# STM32H745.net
KiCad netlist of a schematic drawn in Altium Designer
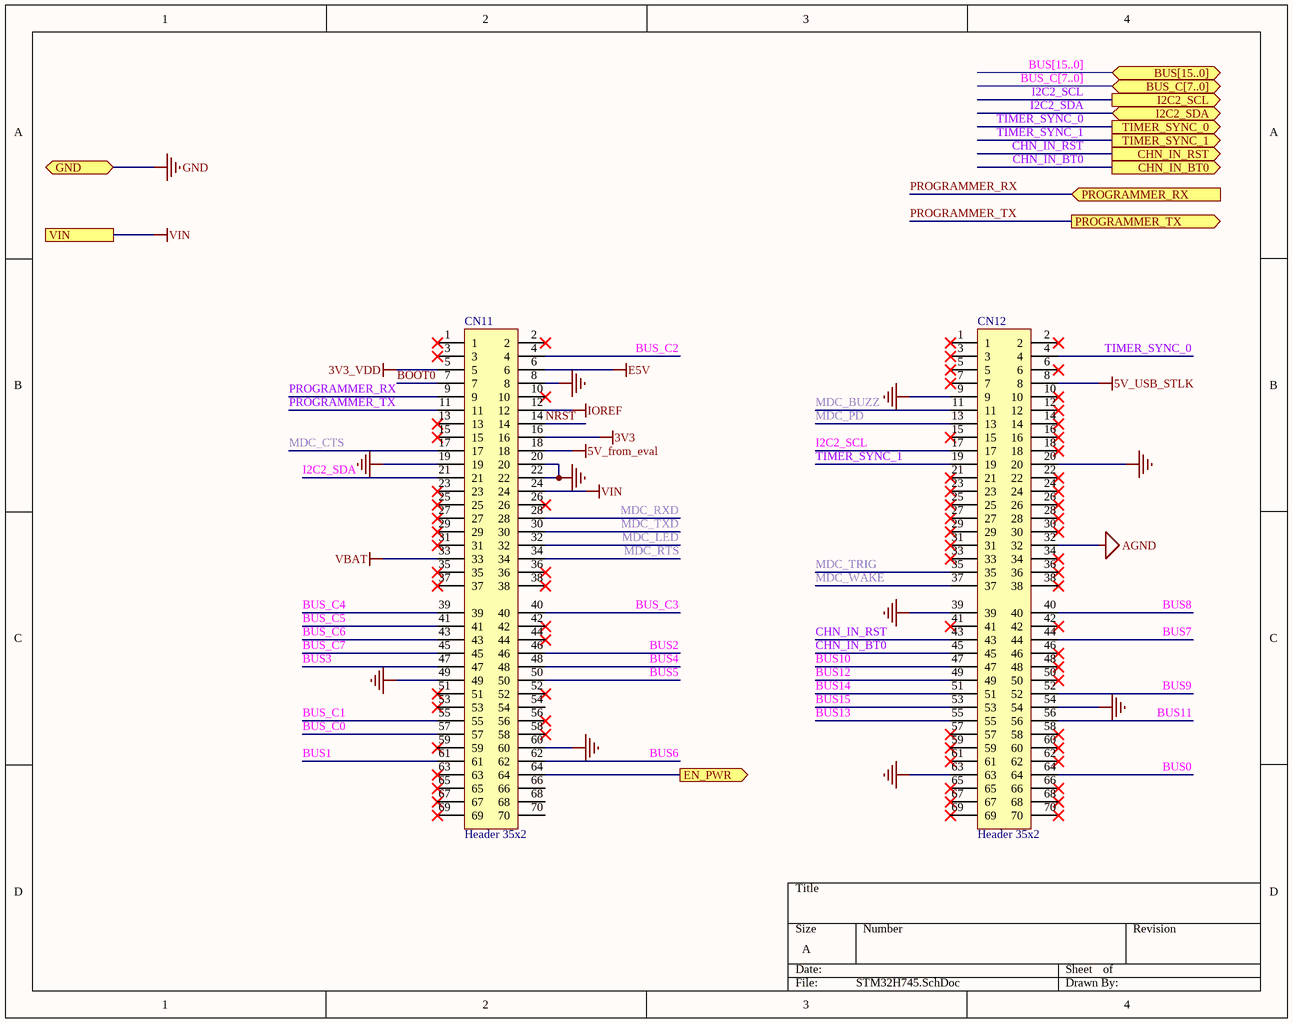
[diagram p0: STM32H745.SchDoc]

(export (version "E")
  (design (tool "Eeschema 10.0.6"))
  (components
    (comp (ref "CN11")
      (value "Header 35x2")
      (footprint "HDR_2x36_2R54_V_M")
      (description "Header, 35x2, 2,54mm, VR, TH, Height 5.84mm/2.54mm")
      (libsource (lib "mantarray_library") (part "MCD-01210"))
    )
    (comp (ref "CN12")
      (value "Header 35x2")
      (footprint "HDR_2x36_2R54_V_M")
      (description "Header, 35x2, 2,54mm, VR, TH, Height 5.84mm/2.54mm")
      (libsource (lib "mantarray_library") (part "MCD-01210"))
    )
  )
  (nets
    (net (code "1") (name "/BOOT0") (class "Default")
      (node (ref "CN11") (pin "7") (pinfunction "7_7") (pintype "passive"))
    )
    (net (code "2") (name "/BUS0") (class "Default")
      (node (ref "CN12") (pin "64") (pinfunction "64_64") (pintype "passive"))
    )
    (net (code "3") (name "/BUS1") (class "Default")
      (node (ref "CN11") (pin "61") (pinfunction "61_61") (pintype "passive"))
    )
    (net (code "4") (name "/BUS2") (class "Default")
      (node (ref "CN11") (pin "46") (pinfunction "46_46") (pintype "passive"))
    )
    (net (code "5") (name "/BUS3") (class "Default")
      (node (ref "CN11") (pin "47") (pinfunction "47_47") (pintype "passive"))
    )
    (net (code "6") (name "/BUS4") (class "Default")
      (node (ref "CN11") (pin "48") (pinfunction "48_48") (pintype "passive"))
    )
    (net (code "7") (name "/BUS5") (class "Default")
      (node (ref "CN11") (pin "50") (pinfunction "50_50") (pintype "passive"))
    )
    (net (code "8") (name "/BUS6") (class "Default")
      (node (ref "CN11") (pin "62") (pinfunction "62_62") (pintype "passive"))
    )
    (net (code "9") (name "/BUS7") (class "Default")
      (node (ref "CN12") (pin "44") (pinfunction "44_44") (pintype "passive"))
    )
    (net (code "10") (name "/BUS8") (class "Default")
      (node (ref "CN12") (pin "40") (pinfunction "40_40") (pintype "passive"))
    )
    (net (code "11") (name "/BUS9") (class "Default")
      (node (ref "CN12") (pin "52") (pinfunction "52_52") (pintype "passive"))
    )
    (net (code "12") (name "/BUS10") (class "Default")
      (node (ref "CN12") (pin "47") (pinfunction "47_47") (pintype "passive"))
    )
    (net (code "13") (name "/BUS11") (class "Default")
      (node (ref "CN12") (pin "56") (pinfunction "56_56") (pintype "passive"))
    )
    (net (code "14") (name "/BUS12") (class "Default")
      (node (ref "CN12") (pin "49") (pinfunction "49_49") (pintype "passive"))
    )
    (net (code "15") (name "/BUS13") (class "Default")
      (node (ref "CN12") (pin "55") (pinfunction "55_55") (pintype "passive"))
    )
    (net (code "16") (name "/BUS14") (class "Default")
      (node (ref "CN12") (pin "51") (pinfunction "51_51") (pintype "passive"))
    )
    (net (code "17") (name "/BUS15") (class "Default")
      (node (ref "CN12") (pin "53") (pinfunction "53_53") (pintype "passive"))
    )
    (net (code "19") (name "/BUS_C0") (class "Default")
      (node (ref "CN11") (pin "57") (pinfunction "57_57") (pintype "passive"))
    )
    (net (code "20") (name "/BUS_C1") (class "Default")
      (node (ref "CN11") (pin "55") (pinfunction "55_55") (pintype "passive"))
    )
    (net (code "21") (name "/BUS_C2") (class "Default")
      (node (ref "CN11") (pin "4") (pinfunction "4_4") (pintype "passive"))
    )
    (net (code "22") (name "/BUS_C3") (class "Default")
      (node (ref "CN11") (pin "40") (pinfunction "40_40") (pintype "passive"))
    )
    (net (code "23") (name "/BUS_C4") (class "Default")
      (node (ref "CN11") (pin "39") (pinfunction "39_39") (pintype "passive"))
    )
    (net (code "24") (name "/BUS_C5") (class "Default")
      (node (ref "CN11") (pin "41") (pinfunction "41_41") (pintype "passive"))
    )
    (net (code "25") (name "/BUS_C6") (class "Default")
      (node (ref "CN11") (pin "43") (pinfunction "43_43") (pintype "passive"))
    )
    (net (code "26") (name "/BUS_C7") (class "Default")
      (node (ref "CN11") (pin "45") (pinfunction "45_45") (pintype "passive"))
    )
    (net (code "28") (name "/CHN_IN_BT0") (class "Default")
      (node (ref "CN12") (pin "45") (pinfunction "45_45") (pintype "passive"))
    )
    (net (code "29") (name "/CHN_IN_RST") (class "Default")
      (node (ref "CN12") (pin "43") (pinfunction "43_43") (pintype "passive"))
    )
    (net (code "30") (name "/EN_PWR") (class "Default")
      (node (ref "CN11") (pin "64") (pinfunction "64_64") (pintype "passive"))
    )
    (net (code "31") (name "/I2C2_SCL") (class "Default")
      (node (ref "CN12") (pin "17") (pinfunction "17_17") (pintype "passive"))
    )
    (net (code "32") (name "/I2C2_SDA") (class "Default")
      (node (ref "CN11") (pin "21") (pinfunction "21_21") (pintype "passive"))
    )
    (net (code "33") (name "/MDC_BUZZ") (class "Default")
      (node (ref "CN12") (pin "11") (pinfunction "11_11") (pintype "passive"))
    )
    (net (code "34") (name "/MDC_CTS") (class "Default")
      (node (ref "CN11") (pin "17") (pinfunction "17_17") (pintype "passive"))
    )
    (net (code "35") (name "/MDC_LED") (class "Default")
      (node (ref "CN11") (pin "32") (pinfunction "32_32") (pintype "passive"))
    )
    (net (code "36") (name "/MDC_PD") (class "Default")
      (node (ref "CN12") (pin "13") (pinfunction "13_13") (pintype "passive"))
    )
    (net (code "37") (name "/MDC_RTS") (class "Default")
      (node (ref "CN11") (pin "34") (pinfunction "34_34") (pintype "passive"))
    )
    (net (code "38") (name "/MDC_RXD") (class "Default")
      (node (ref "CN11") (pin "28") (pinfunction "28_28") (pintype "passive"))
    )
    (net (code "39") (name "/MDC_TRIG") (class "Default")
      (node (ref "CN12") (pin "35") (pinfunction "35_35") (pintype "passive"))
    )
    (net (code "40") (name "/MDC_TXD") (class "Default")
      (node (ref "CN11") (pin "30") (pinfunction "30_30") (pintype "passive"))
    )
    (net (code "41") (name "/MDC_WAKE") (class "Default")
      (node (ref "CN12") (pin "37") (pinfunction "37_37") (pintype "passive"))
    )
    (net (code "42") (name "/NRST") (class "Default")
      (node (ref "CN11") (pin "14") (pinfunction "14_14") (pintype "passive"))
    )
    (net (code "43") (name "/PROGRAMMER_RX") (class "Default")
      (node (ref "CN11") (pin "9") (pinfunction "9_9") (pintype "passive"))
    )
    (net (code "44") (name "/PROGRAMMER_TX") (class "Default")
      (node (ref "CN11") (pin "11") (pinfunction "11_11") (pintype "passive"))
    )
    (net (code "45") (name "/TIMER_SYNC_0") (class "Default")
      (node (ref "CN12") (pin "4") (pinfunction "4_4") (pintype "passive"))
    )
    (net (code "46") (name "/TIMER_SYNC_1") (class "Default")
      (node (ref "CN12") (pin "19") (pinfunction "19_19") (pintype "passive"))
    )
    (net (code "47") (name "3V3") (class "Default")
      (node (ref "CN11") (pin "16") (pinfunction "16_16") (pintype "passive"))
    )
    (net (code "48") (name "3V3_VDD") (class "Default")
      (node (ref "CN11") (pin "5") (pinfunction "5_5") (pintype "passive"))
    )
    (net (code "49") (name "5V_USB_STLK") (class "Default")
      (node (ref "CN12") (pin "8") (pinfunction "8_8") (pintype "passive"))
    )
    (net (code "50") (name "5V_from_eval") (class "Default")
      (node (ref "CN11") (pin "18") (pinfunction "18_18") (pintype "passive"))
    )
    (net (code "51") (name "AGND") (class "Default")
      (node (ref "CN12") (pin "32") (pinfunction "32_32") (pintype "passive"))
    )
    (net (code "52") (name "E5V") (class "Default")
      (node (ref "CN11") (pin "6") (pinfunction "6_6") (pintype "passive"))
    )
    (net (code "53") (name "GND") (class "Default")
      (node (ref "CN11") (pin "19") (pinfunction "19_19") (pintype "passive"))
      (node (ref "CN11") (pin "20") (pinfunction "20_20") (pintype "passive"))
      (node (ref "CN11") (pin "22") (pinfunction "22_22") (pintype "passive"))
      (node (ref "CN11") (pin "49") (pinfunction "49_49") (pintype "passive"))
      (node (ref "CN11") (pin "60") (pinfunction "60_60") (pintype "passive"))
      (node (ref "CN11") (pin "8") (pinfunction "8_8") (pintype "passive"))
      (node (ref "CN12") (pin "20") (pinfunction "20_20") (pintype "passive"))
      (node (ref "CN12") (pin "39") (pinfunction "39_39") (pintype "passive"))
      (node (ref "CN12") (pin "54") (pinfunction "54_54") (pintype "passive"))
      (node (ref "CN12") (pin "63") (pinfunction "63_63") (pintype "passive"))
      (node (ref "CN12") (pin "9") (pinfunction "9_9") (pintype "passive"))
    )
    (net (code "54") (name "IOREF") (class "Default")
      (node (ref "CN11") (pin "12") (pinfunction "12_12") (pintype "passive"))
    )
    (net (code "55") (name "VBAT") (class "Default")
      (node (ref "CN11") (pin "33") (pinfunction "33_33") (pintype "passive"))
    )
    (net (code "56") (name "VIN") (class "Default")
      (node (ref "CN11") (pin "24") (pinfunction "24_24") (pintype "passive"))
    )
    (net (code "57") (name "unconnected-(CN11-Pad1)") (class "Default")
      (node (ref "CN11") (pin "1") (pinfunction "1_1") (pintype "passive+no_connect"))
    )
    (net (code "58") (name "unconnected-(CN11-Pad2)") (class "Default")
      (node (ref "CN11") (pin "2") (pinfunction "2_2") (pintype "passive+no_connect"))
    )
    (net (code "59") (name "unconnected-(CN11-Pad3)") (class "Default")
      (node (ref "CN11") (pin "3") (pinfunction "3_3") (pintype "passive+no_connect"))
    )
    (net (code "60") (name "unconnected-(CN11-Pad10)") (class "Default")
      (node (ref "CN11") (pin "10") (pinfunction "10_10") (pintype "passive+no_connect"))
    )
    (net (code "61") (name "unconnected-(CN11-Pad13)") (class "Default")
      (node (ref "CN11") (pin "13") (pinfunction "13_13") (pintype "passive+no_connect"))
    )
    (net (code "62") (name "unconnected-(CN11-Pad15)") (class "Default")
      (node (ref "CN11") (pin "15") (pinfunction "15_15") (pintype "passive+no_connect"))
    )
    (net (code "63") (name "unconnected-(CN11-Pad23)") (class "Default")
      (node (ref "CN11") (pin "23") (pinfunction "23_23") (pintype "passive+no_connect"))
    )
    (net (code "64") (name "unconnected-(CN11-Pad25)") (class "Default")
      (node (ref "CN11") (pin "25") (pinfunction "25_25") (pintype "passive+no_connect"))
    )
    (net (code "65") (name "unconnected-(CN11-Pad26)") (class "Default")
      (node (ref "CN11") (pin "26") (pinfunction "26_26") (pintype "passive+no_connect"))
    )
    (net (code "66") (name "unconnected-(CN11-Pad27)") (class "Default")
      (node (ref "CN11") (pin "27") (pinfunction "27_27") (pintype "passive+no_connect"))
    )
    (net (code "67") (name "unconnected-(CN11-Pad29)") (class "Default")
      (node (ref "CN11") (pin "29") (pinfunction "29_29") (pintype "passive+no_connect"))
    )
    (net (code "68") (name "unconnected-(CN11-Pad31)") (class "Default")
      (node (ref "CN11") (pin "31") (pinfunction "31_31") (pintype "passive+no_connect"))
    )
    (net (code "69") (name "unconnected-(CN11-Pad35)") (class "Default")
      (node (ref "CN11") (pin "35") (pinfunction "35_35") (pintype "passive+no_connect"))
    )
    (net (code "70") (name "unconnected-(CN11-Pad36)") (class "Default")
      (node (ref "CN11") (pin "36") (pinfunction "36_36") (pintype "passive+no_connect"))
    )
    (net (code "71") (name "unconnected-(CN11-Pad37)") (class "Default")
      (node (ref "CN11") (pin "37") (pinfunction "37_37") (pintype "passive+no_connect"))
    )
    (net (code "72") (name "unconnected-(CN11-Pad38)") (class "Default")
      (node (ref "CN11") (pin "38") (pinfunction "38_38") (pintype "passive+no_connect"))
    )
    (net (code "73") (name "unconnected-(CN11-Pad42)") (class "Default")
      (node (ref "CN11") (pin "42") (pinfunction "42_42") (pintype "passive+no_connect"))
    )
    (net (code "74") (name "unconnected-(CN11-Pad44)") (class "Default")
      (node (ref "CN11") (pin "44") (pinfunction "44_44") (pintype "passive+no_connect"))
    )
    (net (code "75") (name "unconnected-(CN11-Pad51)") (class "Default")
      (node (ref "CN11") (pin "51") (pinfunction "51_51") (pintype "passive+no_connect"))
    )
    (net (code "76") (name "unconnected-(CN11-Pad52)") (class "Default")
      (node (ref "CN11") (pin "52") (pinfunction "52_52") (pintype "passive+no_connect"))
    )
    (net (code "77") (name "unconnected-(CN11-Pad53)") (class "Default")
      (node (ref "CN11") (pin "53") (pinfunction "53_53") (pintype "passive+no_connect"))
    )
    (net (code "78") (name "unconnected-(CN11-Pad54)") (class "Default")
      (node (ref "CN11") (pin "54") (pinfunction "54_54") (pintype "passive"))
    )
    (net (code "79") (name "unconnected-(CN11-Pad56)") (class "Default")
      (node (ref "CN11") (pin "56") (pinfunction "56_56") (pintype "passive+no_connect"))
    )
    (net (code "80") (name "unconnected-(CN11-Pad58)") (class "Default")
      (node (ref "CN11") (pin "58") (pinfunction "58_58") (pintype "passive+no_connect"))
    )
    (net (code "81") (name "unconnected-(CN11-Pad59)") (class "Default")
      (node (ref "CN11") (pin "59") (pinfunction "59_59") (pintype "passive+no_connect"))
    )
    (net (code "82") (name "unconnected-(CN11-Pad63)") (class "Default")
      (node (ref "CN11") (pin "63") (pinfunction "63_63") (pintype "passive+no_connect"))
    )
    (net (code "83") (name "unconnected-(CN11-Pad65)") (class "Default")
      (node (ref "CN11") (pin "65") (pinfunction "65_65") (pintype "passive+no_connect"))
    )
    (net (code "84") (name "unconnected-(CN11-Pad66)") (class "Default")
      (node (ref "CN11") (pin "66") (pinfunction "66_66") (pintype "passive"))
    )
    (net (code "85") (name "unconnected-(CN11-Pad67)") (class "Default")
      (node (ref "CN11") (pin "67") (pinfunction "67_67") (pintype "passive+no_connect"))
    )
    (net (code "86") (name "unconnected-(CN11-Pad68)") (class "Default")
      (node (ref "CN11") (pin "68") (pinfunction "68_68") (pintype "passive"))
    )
    (net (code "87") (name "unconnected-(CN11-Pad69)") (class "Default")
      (node (ref "CN11") (pin "69") (pinfunction "69_69") (pintype "passive+no_connect"))
    )
    (net (code "88") (name "unconnected-(CN11-Pad70)") (class "Default")
      (node (ref "CN11") (pin "70") (pinfunction "70_70") (pintype "passive"))
    )
    (net (code "89") (name "unconnected-(CN12-Pad1)") (class "Default")
      (node (ref "CN12") (pin "1") (pinfunction "1_1") (pintype "passive+no_connect"))
    )
    (net (code "90") (name "unconnected-(CN12-Pad2)") (class "Default")
      (node (ref "CN12") (pin "2") (pinfunction "2_2") (pintype "passive+no_connect"))
    )
    (net (code "91") (name "unconnected-(CN12-Pad3)") (class "Default")
      (node (ref "CN12") (pin "3") (pinfunction "3_3") (pintype "passive+no_connect"))
    )
    (net (code "92") (name "unconnected-(CN12-Pad5)") (class "Default")
      (node (ref "CN12") (pin "5") (pinfunction "5_5") (pintype "passive+no_connect"))
    )
    (net (code "93") (name "unconnected-(CN12-Pad6)") (class "Default")
      (node (ref "CN12") (pin "6") (pinfunction "6_6") (pintype "passive+no_connect"))
    )
    (net (code "94") (name "unconnected-(CN12-Pad7)") (class "Default")
      (node (ref "CN12") (pin "7") (pinfunction "7_7") (pintype "passive+no_connect"))
    )
    (net (code "95") (name "unconnected-(CN12-Pad10)") (class "Default")
      (node (ref "CN12") (pin "10") (pinfunction "10_10") (pintype "passive+no_connect"))
    )
    (net (code "96") (name "unconnected-(CN12-Pad12)") (class "Default")
      (node (ref "CN12") (pin "12") (pinfunction "12_12") (pintype "passive+no_connect"))
    )
    (net (code "97") (name "unconnected-(CN12-Pad14)") (class "Default")
      (node (ref "CN12") (pin "14") (pinfunction "14_14") (pintype "passive+no_connect"))
    )
    (net (code "98") (name "unconnected-(CN12-Pad15)") (class "Default")
      (node (ref "CN12") (pin "15") (pinfunction "15_15") (pintype "passive+no_connect"))
    )
    (net (code "99") (name "unconnected-(CN12-Pad16)") (class "Default")
      (node (ref "CN12") (pin "16") (pinfunction "16_16") (pintype "passive+no_connect"))
    )
    (net (code "100") (name "unconnected-(CN12-Pad18)") (class "Default")
      (node (ref "CN12") (pin "18") (pinfunction "18_18") (pintype "passive+no_connect"))
    )
    (net (code "101") (name "unconnected-(CN12-Pad21)") (class "Default")
      (node (ref "CN12") (pin "21") (pinfunction "21_21") (pintype "passive+no_connect"))
    )
    (net (code "102") (name "unconnected-(CN12-Pad22)") (class "Default")
      (node (ref "CN12") (pin "22") (pinfunction "22_22") (pintype "passive+no_connect"))
    )
    (net (code "103") (name "unconnected-(CN12-Pad23)") (class "Default")
      (node (ref "CN12") (pin "23") (pinfunction "23_23") (pintype "passive+no_connect"))
    )
    (net (code "104") (name "unconnected-(CN12-Pad24)") (class "Default")
      (node (ref "CN12") (pin "24") (pinfunction "24_24") (pintype "passive+no_connect"))
    )
    (net (code "105") (name "unconnected-(CN12-Pad25)") (class "Default")
      (node (ref "CN12") (pin "25") (pinfunction "25_25") (pintype "passive+no_connect"))
    )
    (net (code "106") (name "unconnected-(CN12-Pad26)") (class "Default")
      (node (ref "CN12") (pin "26") (pinfunction "26_26") (pintype "passive+no_connect"))
    )
    (net (code "107") (name "unconnected-(CN12-Pad27)") (class "Default")
      (node (ref "CN12") (pin "27") (pinfunction "27_27") (pintype "passive+no_connect"))
    )
    (net (code "108") (name "unconnected-(CN12-Pad28)") (class "Default")
      (node (ref "CN12") (pin "28") (pinfunction "28_28") (pintype "passive+no_connect"))
    )
    (net (code "109") (name "unconnected-(CN12-Pad29)") (class "Default")
      (node (ref "CN12") (pin "29") (pinfunction "29_29") (pintype "passive+no_connect"))
    )
    (net (code "110") (name "unconnected-(CN12-Pad30)") (class "Default")
      (node (ref "CN12") (pin "30") (pinfunction "30_30") (pintype "passive+no_connect"))
    )
    (net (code "111") (name "unconnected-(CN12-Pad31)") (class "Default")
      (node (ref "CN12") (pin "31") (pinfunction "31_31") (pintype "passive+no_connect"))
    )
    (net (code "112") (name "unconnected-(CN12-Pad33)") (class "Default")
      (node (ref "CN12") (pin "33") (pinfunction "33_33") (pintype "passive+no_connect"))
    )
    (net (code "113") (name "unconnected-(CN12-Pad34)") (class "Default")
      (node (ref "CN12") (pin "34") (pinfunction "34_34") (pintype "passive+no_connect"))
    )
    (net (code "114") (name "unconnected-(CN12-Pad36)") (class "Default")
      (node (ref "CN12") (pin "36") (pinfunction "36_36") (pintype "passive+no_connect"))
    )
    (net (code "115") (name "unconnected-(CN12-Pad38)") (class "Default")
      (node (ref "CN12") (pin "38") (pinfunction "38_38") (pintype "passive+no_connect"))
    )
    (net (code "116") (name "unconnected-(CN12-Pad41)") (class "Default")
      (node (ref "CN12") (pin "41") (pinfunction "41_41") (pintype "passive+no_connect"))
    )
    (net (code "117") (name "unconnected-(CN12-Pad42)") (class "Default")
      (node (ref "CN12") (pin "42") (pinfunction "42_42") (pintype "passive+no_connect"))
    )
    (net (code "118") (name "unconnected-(CN12-Pad46)") (class "Default")
      (node (ref "CN12") (pin "46") (pinfunction "46_46") (pintype "passive+no_connect"))
    )
    (net (code "119") (name "unconnected-(CN12-Pad48)") (class "Default")
      (node (ref "CN12") (pin "48") (pinfunction "48_48") (pintype "passive+no_connect"))
    )
    (net (code "120") (name "unconnected-(CN12-Pad50)") (class "Default")
      (node (ref "CN12") (pin "50") (pinfunction "50_50") (pintype "passive+no_connect"))
    )
    (net (code "121") (name "unconnected-(CN12-Pad57)") (class "Default")
      (node (ref "CN12") (pin "57") (pinfunction "57_57") (pintype "passive+no_connect"))
    )
    (net (code "122") (name "unconnected-(CN12-Pad58)") (class "Default")
      (node (ref "CN12") (pin "58") (pinfunction "58_58") (pintype "passive+no_connect"))
    )
    (net (code "123") (name "unconnected-(CN12-Pad59)") (class "Default")
      (node (ref "CN12") (pin "59") (pinfunction "59_59") (pintype "passive+no_connect"))
    )
    (net (code "124") (name "unconnected-(CN12-Pad60)") (class "Default")
      (node (ref "CN12") (pin "60") (pinfunction "60_60") (pintype "passive+no_connect"))
    )
    (net (code "125") (name "unconnected-(CN12-Pad61)") (class "Default")
      (node (ref "CN12") (pin "61") (pinfunction "61_61") (pintype "passive+no_connect"))
    )
    (net (code "126") (name "unconnected-(CN12-Pad62)") (class "Default")
      (node (ref "CN12") (pin "62") (pinfunction "62_62") (pintype "passive+no_connect"))
    )
    (net (code "127") (name "unconnected-(CN12-Pad65)") (class "Default")
      (node (ref "CN12") (pin "65") (pinfunction "65_65") (pintype "passive+no_connect"))
    )
    (net (code "128") (name "unconnected-(CN12-Pad66)") (class "Default")
      (node (ref "CN12") (pin "66") (pinfunction "66_66") (pintype "passive+no_connect"))
    )
    (net (code "129") (name "unconnected-(CN12-Pad67)") (class "Default")
      (node (ref "CN12") (pin "67") (pinfunction "67_67") (pintype "passive+no_connect"))
    )
    (net (code "130") (name "unconnected-(CN12-Pad68)") (class "Default")
      (node (ref "CN12") (pin "68") (pinfunction "68_68") (pintype "passive+no_connect"))
    )
    (net (code "131") (name "unconnected-(CN12-Pad69)") (class "Default")
      (node (ref "CN12") (pin "69") (pinfunction "69_69") (pintype "passive+no_connect"))
    )
    (net (code "132") (name "unconnected-(CN12-Pad70)") (class "Default")
      (node (ref "CN12") (pin "70") (pinfunction "70_70") (pintype "passive+no_connect"))
    )
  )
)
